# SimPL_IMU_v1_0_NOV23.net
KiCad netlist of a schematic drawn in Altium Designer
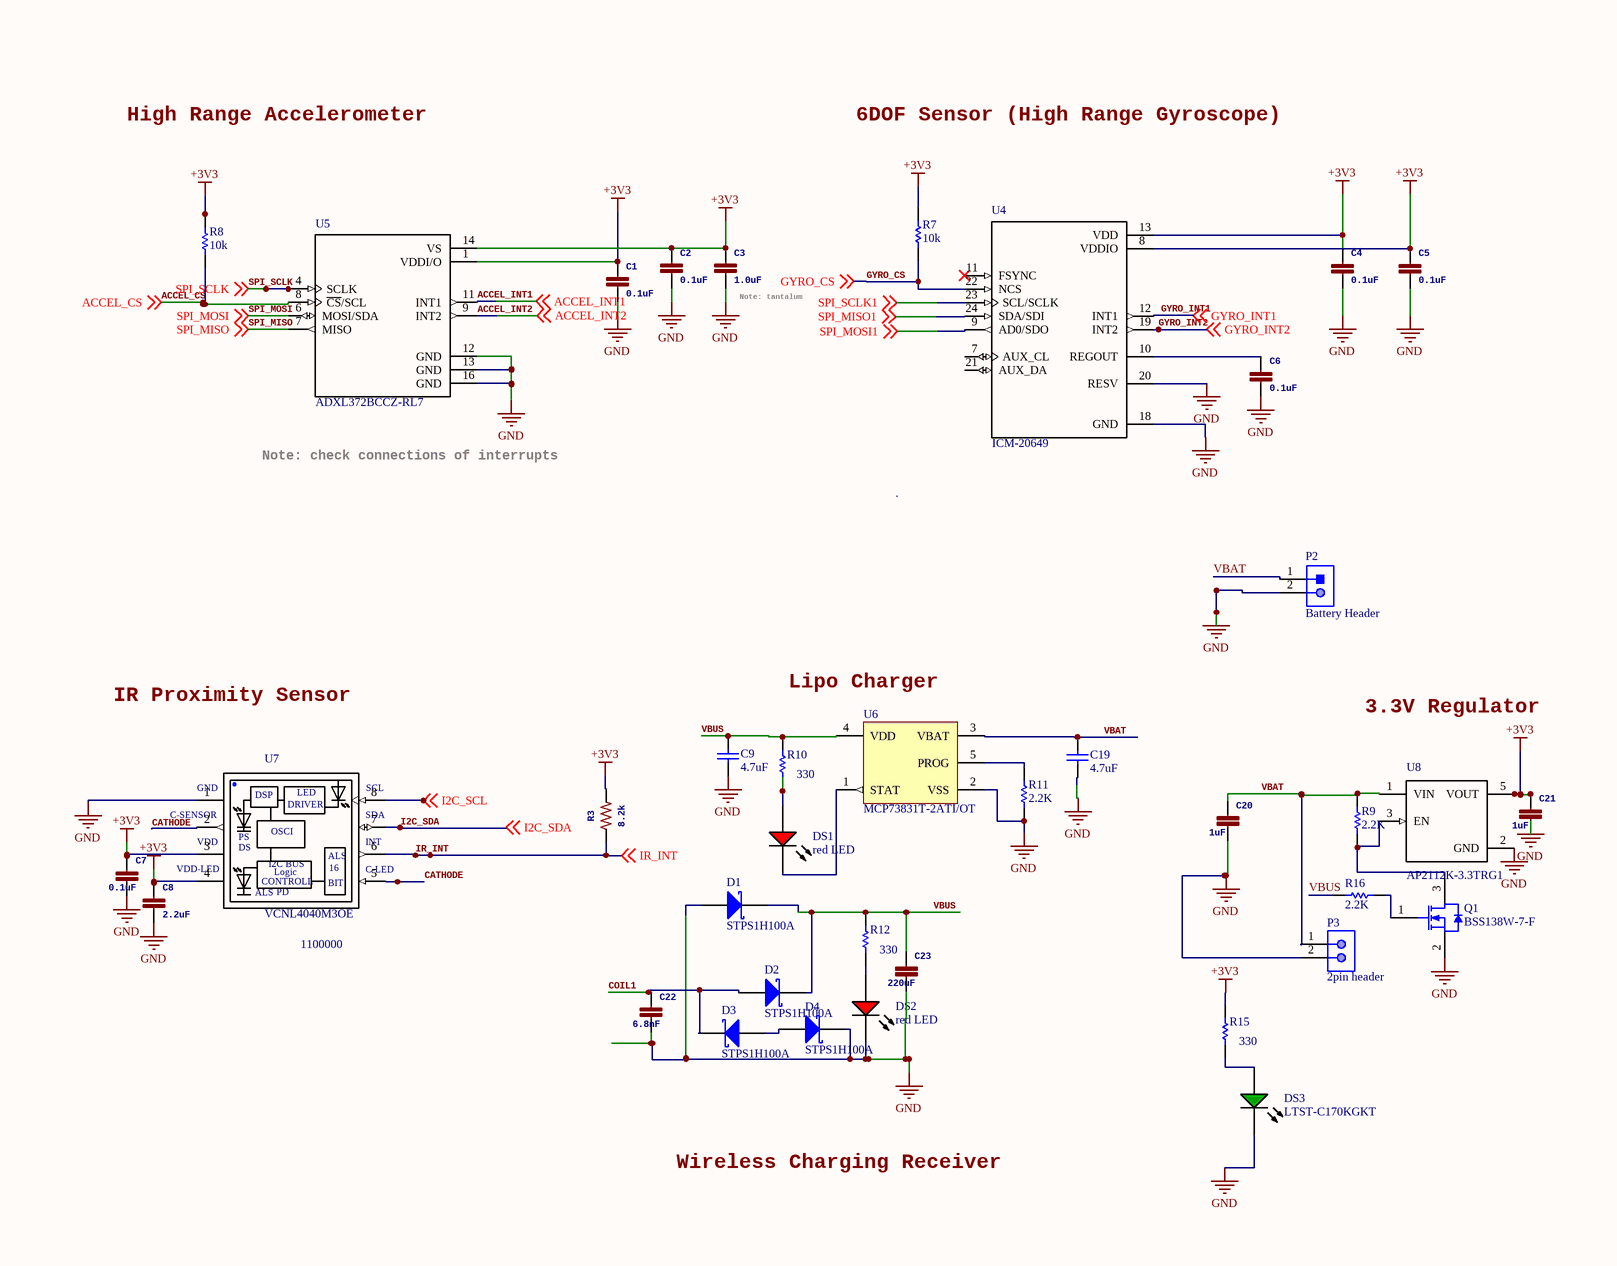
[diagram p0: SimPL_IMU_v1_0_NOV23.SchDoc]

(export (version "E")
  (design (tool "Eeschema 10.0.6"))
  (components
    (comp (ref "C1")
      (value "0.1uF")
      (footprint "0402")
      (libsource (lib "SparkFun-Capacitors") (part "0.1UF-0402-16V-10%"))
    )
    (comp (ref "C2")
      (value "0.1uF")
      (footprint "0402")
      (libsource (lib "SparkFun-Capacitors") (part "0.1UF-0402-16V-10%"))
    )
    (comp (ref "C3")
      (value "1.0uF")
      (footprint "0402")
      (libsource (lib "SparkFun-Capacitors") (part "1.0UF-0402-16V-10%"))
    )
    (comp (ref "C4")
      (value "0.1uF")
      (footprint "0402")
      (libsource (lib "SparkFun-Capacitors") (part "0.1UF-0402-16V-10%"))
    )
    (comp (ref "C5")
      (value "0.1uF")
      (footprint "0402")
      (libsource (lib "SparkFun-Capacitors") (part "0.1UF-0402-16V-10%"))
    )
    (comp (ref "C6")
      (value "0.1uF")
      (footprint "0402")
      (libsource (lib "SparkFun-Capacitors") (part "0.1UF-0402-16V-10%"))
    )
    (comp (ref "C7")
      (value "0.1uF")
      (footprint "0402")
      (libsource (lib "SparkFun-Capacitors") (part "0.1UF-0402-16V-10%"))
    )
    (comp (ref "C8")
      (value "2.2uF")
      (footprint "0402")
      (libsource (lib "SparkFun-Capacitors") (part "0.1UF-0402-16V-10%"))
    )
    (comp (ref "C9")
      (value "4.7uF")
      (footprint "CAPC1005X65X10ML15")
      (description "Chip Capacitor, 4.7 uF, +/- 20%, 10 V, -55 to 85 degC, 0402 (1005 Metric), RoHS, Tape and Reel")
      (fields
        (field (name "TOLERANCE") "±20%")
        (field (name "PCN PART NUMBER") "MLCCPartNumberChange30/Nov/2012")
      )
      (libsource (lib "Altium Content Vault") (part "CAP-NP-2"))
    )
    (comp (ref "C19")
      (value "4.7uF")
      (footprint "CAPC1005X65X10ML15")
      (description "Chip Capacitor, 4.7 uF, +/- 20%, 10 V, -55 to 85 degC, 0402 (1005 Metric), RoHS, Tape and Reel")
      (fields
        (field (name "TOLERANCE") "±20%")
        (field (name "PCN PART NUMBER") "MLCCPartNumberChange30/Nov/2012")
      )
      (libsource (lib "Altium Content Vault") (part "CAP-NP-2"))
    )
    (comp (ref "C20")
      (value "1uF")
      (footprint "0402")
      (libsource (lib "SparkFun-Capacitors") (part "0.1UF-0402-16V-10%"))
    )
    (comp (ref "C21")
      (value "1uF")
      (footprint "0402")
      (libsource (lib "SparkFun-Capacitors") (part "0.1UF-0402-16V-10%"))
    )
    (comp (ref "C22")
      (value "6.8nF")
      (footprint "0402")
      (libsource (lib "SparkFun-Capacitors") (part "0.1UF-0402-16V-10%"))
    )
    (comp (ref "C23")
      (value "220uF")
      (footprint "0402")
      (libsource (lib "SparkFun-Capacitors") (part "0.1UF-0402-16V-10%"))
    )
    (comp (ref "D1")
      (value "STPS1H100A")
      (footprint "STM-SMA-2_V")
      (description "High Voltage Power Schottky Rectifier, 1 A, 100 V, 2-Pin SMD (SMA), RoHS, Tape and Reel")
      (fields (field (name "MANUFACTURER") "STMicroelectronics"))
      (libsource (lib "Altium Content Vault") (part "DSKY-AK-2"))
    )
    (comp (ref "D2")
      (value "STPS1H100A")
      (footprint "STM-SMA-2_V")
      (description "High Voltage Power Schottky Rectifier, 1 A, 100 V, 2-Pin SMD (SMA), RoHS, Tape and Reel")
      (fields (field (name "MANUFACTURER") "STMicroelectronics"))
      (libsource (lib "Altium Content Vault") (part "DSKY-AK-2"))
    )
    (comp (ref "D3")
      (value "STPS1H100A")
      (footprint "STM-SMA-2_V")
      (description "High Voltage Power Schottky Rectifier, 1 A, 100 V, 2-Pin SMD (SMA), RoHS, Tape and Reel")
      (fields (field (name "MANUFACTURER") "STMicroelectronics"))
      (libsource (lib "Altium Content Vault") (part "DSKY-AK-2"))
    )
    (comp (ref "D4")
      (value "STPS1H100A")
      (footprint "STM-SMA-2_V")
      (description "High Voltage Power Schottky Rectifier, 1 A, 100 V, 2-Pin SMD (SMA), RoHS, Tape and Reel")
      (fields (field (name "MANUFACTURER") "STMicroelectronics"))
      (libsource (lib "Altium Content Vault") (part "DSKY-AK-2"))
    )
    (comp (ref "DS1")
      (value "red LED")
      (footprint "VISH-TLMS1000_V")
      (description "Low Current LED, 40 mW, 1.8 V, -40 to 100 degC, 2-Pin SMD (0603), RoHS, Tape and Reel")
      (fields (field (name "MANUFACTURER") "Vishay"))
      (libsource (lib "Altium Content Vault") (part "LED-RED-AK-2"))
    )
    (comp (ref "DS2")
      (value "red LED")
      (footprint "VISH-TLMS1000_V")
      (description "Low Current LED, 40 mW, 1.8 V, -40 to 100 degC, 2-Pin SMD (0603), RoHS, Tape and Reel")
      (fields (field (name "MANUFACTURER") "Vishay"))
      (libsource (lib "Altium Content Vault") (part "LED-RED-AK-2"))
    )
    (comp (ref "DS3")
      (value "LTST-C170KGKT")
      (footprint "LTST-LTST-C170KGKT-2_V")
      (description "Ultra Bright AlInGaP Chip LED, 75 mW, -55 to 85 degC, 2-Pin SMD (0805), RoHS, Tape and Reel")
      (fields (field (name "MANUFACTURER") "Lite-On"))
      (libsource (lib "Altium Content Vault") (part "LED-GREEN-KA-2"))
    )
    (comp (ref "P2")
      (value "Battery Header")
      (footprint "JST-S2B-PH-K-S_V")
      (fields (field (name "TOLERANCE") "20%"))
      (libsource (lib "Altium Content Vault") (part "CN-1P-M-R2"))
    )
    (comp (ref "P3")
      (value "2pin header")
      (footprint "AMPH-68000-102HLF_V")
      (description "Male Header, Pitch 2.54 mm, 1 x 2 Position, Height 8.38 mm, Tail Length 2.41 mm, RoHS, Bulk")
      (fields (field (name "MANUFACTURER") "FCI"))
      (libsource (lib "") (part "CN-1P-M-R2_1"))
    )
    (comp (ref "Q1")
      (value "BSS138W-7-F")
      (footprint "DIOD-SOT323-3_V")
      (fields (field (name "MANUFACTURER") "DiodesIncorporated"))
      (libsource (lib "Altium Content Vault") (part "NEMOS-GSD-3"))
    )
    (comp (ref "R3")
      (value "8.2k")
      (footprint "0603")
      (libsource (lib "SparkFun-Resistors") (part "8.2KOHM-0603-1/10W-5%"))
    )
    (comp (ref "R7")
      (value "10k")
      (footprint "RESC1005X40X25NL05T05")
      (description "Chip Resistor, 10 KOhm, +/- 1%, 100 mW, -55 to 155 degC, 0402 (1005 Metric), RoHS, Tape and Reel")
      (fields (field (name "MANUFACTURER") "Basic Passives") (field (name "TOLERANCE") "1%"))
      (libsource (lib "Altium Content Vault") (part "RES-2"))
    )
    (comp (ref "R8")
      (value "10k")
      (footprint "RESC1005X40X25NL05T05")
      (description "Chip Resistor, 10 KOhm, +/- 1%, 100 mW, -55 to 155 degC, 0402 (1005 Metric), RoHS, Tape and Reel")
      (fields (field (name "MANUFACTURER") "Basic Passives") (field (name "TOLERANCE") "1%"))
      (libsource (lib "Altium Content Vault") (part "RES-2"))
    )
    (comp (ref "R9")
      (value "2.2K")
      (footprint "RESC1005X40X25ML10T10")
      (fields (field (name "PART NUMBER") "MC00625W040212K2") (field (name "MANUFACTURER") "Multicomp"))
      (libsource (lib "Altium Content Vault") (part "RES"))
    )
    (comp (ref "R10")
      (value "330")
      (footprint "RESC2013X50X30NL20T20")
      (fields (field (name "MANUFACTURER") "Vishay Dale") (field (name "PART NUMBER") "CRCW0805330RFKEA"))
      (libsource (lib "Altium Content Vault") (part "RES"))
    )
    (comp (ref "R11")
      (value "2.2K")
      (footprint "RESC1005X40X25ML10T10")
      (fields (field (name "PART NUMBER") "MC00625W040212K2") (field (name "MANUFACTURER") "Multicomp"))
      (libsource (lib "Altium Content Vault") (part "RES"))
    )
    (comp (ref "R12")
      (value "330")
      (footprint "RESC2013X50X30NL20T20")
      (fields (field (name "MANUFACTURER") "Vishay Dale") (field (name "PART NUMBER") "CRCW0805330RFKEA"))
      (libsource (lib "Altium Content Vault") (part "RES"))
    )
    (comp (ref "R15")
      (value "330")
      (footprint "RESC2013X50X30NL20T20")
      (fields (field (name "MANUFACTURER") "Vishay Dale") (field (name "PART NUMBER") "CRCW0805330RFKEA"))
      (libsource (lib "Altium Content Vault") (part "RES"))
    )
    (comp (ref "R16")
      (value "2.2K")
      (footprint "RESC1005X40X25ML10T10")
      (fields (field (name "PART NUMBER") "MC00625W040212K2") (field (name "MANUFACTURER") "Multicomp"))
      (libsource (lib "Altium Content Vault") (part "RES"))
    )
    (comp (ref "U4")
      (value "ICM-20649")
      (footprint "*QFN40P300X300X95-24N")
      (description "Wide-Range 6-Axis MEMS MotionTracking Device for Sports and High Impact Applications")
      (fields (field (name "MF") "TDK InvenSense"))
      (libsource (lib "ICM-20649") (part "ICM-20649"))
    )
    (comp (ref "U5")
      (value "ADXL372BCCZ-RL7")
      (footprint "*PQFN50P322X300X114-16N")
      (description "Accelerometer Triple Â±200g 2.5V 16-Pin LGA T/R")
      (fields (field (name "MF") "Analog Devices"))
      (libsource (lib "ADXL372BCCZ-RL7") (part "ADXL372BCCZ-RL7"))
    )
    (comp (ref "U6")
      (value "MCP73831T-2ATI/OT")
      (footprint "SOT-23-OT5_M")
      (libsource (lib "Altium Content Vault") (part "PM-BM-MCP73831-SOT5"))
    )
    (comp (ref "U7")
      (value "VCNL4040M3OE")
      (footprint "*VISHAY_VCNL4040_4X2X1.1")
      (description "VCNL4040 Series 3.6 V 200 mm 16 Bit I2C SMT Proximity and Ambient Light Sensor")
      (fields (field (name "MF") "Vishay"))
      (libsource (lib "VCNL4040M3OE") (part "VCNL4040M3OE"))
    )
    (comp (ref "U8")
      (value "AP2112K-3.3TRG1")
      (footprint "*SOT95P285X140-5N")
      (description "AP2112 Series 0.6 A 3.3 V Fixed Output SMT LDO Linear Regulator - SOT23-5")
      (fields (field (name "MF") "Diodes Inc."))
      (libsource (lib "AP2112K-3.3TRG1") (part "AP2112K-3.3TRG1"))
    )
  )
  (nets
    (net (code "1") (name "+3V3") (class "Default")
      (node (ref "C1") (pin "1") (pinfunction "1_1") (pintype "passive"))
      (node (ref "C2") (pin "1") (pinfunction "1_1") (pintype "passive"))
      (node (ref "C21") (pin "1") (pinfunction "1_1") (pintype "passive"))
      (node (ref "C3") (pin "1") (pinfunction "1_1") (pintype "passive"))
      (node (ref "C4") (pin "1") (pinfunction "1_1") (pintype "passive"))
      (node (ref "C5") (pin "1") (pinfunction "1_1") (pintype "passive"))
      (node (ref "C7") (pin "1") (pinfunction "1_1") (pintype "passive"))
      (node (ref "C8") (pin "1") (pinfunction "1_1") (pintype "passive"))
      (node (ref "R15") (pin "2") (pinfunction "2_2") (pintype "passive"))
      (node (ref "R3") (pin "2") (pinfunction "2_2") (pintype "passive"))
      (node (ref "R7") (pin "2") (pinfunction "2_2") (pintype "passive"))
      (node (ref "R8") (pin "2") (pinfunction "2_2") (pintype "passive"))
      (node (ref "U4") (pin "13") (pinfunction "VDD_13") (pintype "power_in"))
      (node (ref "U4") (pin "8") (pinfunction "VDDIO_8") (pintype "power_in"))
      (node (ref "U5") (pin "1") (pinfunction "VDDI/O_1") (pintype "power_in"))
      (node (ref "U5") (pin "14") (pinfunction "VS_14") (pintype "power_in"))
      (node (ref "U7") (pin "3") (pinfunction "VDD_3") (pintype "power_in"))
      (node (ref "U7") (pin "4") (pinfunction "VDD-LED_4") (pintype "power_in"))
      (node (ref "U8") (pin "5") (pinfunction "VOUT_5") (pintype "power_in"))
    )
    (net (code "2") (name "/CATHODE") (class "Default")
      (node (ref "U7") (pin "2") (pinfunction "C-SENSOR_2") (pintype "output"))
      (node (ref "U7") (pin "5") (pinfunction "C-LED_5") (pintype "input"))
    )
    (net (code "3") (name "/COIL1") (class "Default")
      (node (ref "C22") (pin "1") (pinfunction "1_1") (pintype "passive"))
      (node (ref "D2") (pin "1") (pinfunction "A_1") (pintype "passive"))
      (node (ref "D3") (pin "2") (pinfunction "K_2") (pintype "passive"))
    )
    (net (code "4") (name "/VBAT") (class "Default")
      (node (ref "C19") (pin "2") (pinfunction "2_2") (pintype "passive"))
      (node (ref "C20") (pin "1") (pinfunction "1_1") (pintype "passive"))
      (node (ref "P2") (pin "1") (pinfunction "1_1") (pintype "passive"))
      (node (ref "P3") (pin "1") (pinfunction "1_1") (pintype "passive"))
      (node (ref "R9") (pin "2") (pinfunction "2_2") (pintype "passive"))
      (node (ref "U6") (pin "3") (pinfunction "VBAT_3") (pintype "power_in"))
      (node (ref "U8") (pin "1") (pinfunction "VIN_1") (pintype "power_in"))
    )
    (net (code "5") (name "/VBUS") (class "Default")
      (node (ref "C23") (pin "1") (pinfunction "1_1") (pintype "passive"))
      (node (ref "C9") (pin "2") (pinfunction "2_2") (pintype "passive"))
      (node (ref "D1") (pin "2") (pinfunction "K_2") (pintype "passive"))
      (node (ref "D2") (pin "2") (pinfunction "K_2") (pintype "passive"))
      (node (ref "R10") (pin "2") (pinfunction "2_2") (pintype "passive"))
      (node (ref "R12") (pin "2") (pinfunction "2_2") (pintype "passive"))
      (node (ref "R16") (pin "2") (pinfunction "2_2") (pintype "passive"))
      (node (ref "U6") (pin "4") (pinfunction "VDD_4") (pintype "power_in"))
    )
    (net (code "6") (name "ACCEL_CS") (class "Default")
      (node (ref "R8") (pin "1") (pinfunction "1_1") (pintype "passive"))
      (node (ref "U5") (pin "8") (pinfunction "~{CS}/SCL_8") (pintype "input"))
    )
    (net (code "7") (name "ACCEL_INT1") (class "Default")
      (node (ref "U5") (pin "11") (pinfunction "INT1_11") (pintype "output"))
    )
    (net (code "8") (name "ACCEL_INT2") (class "Default")
      (node (ref "U5") (pin "9") (pinfunction "INT2_9") (pintype "output"))
    )
    (net (code "9") (name "GND") (class "Default")
      (node (ref "C1") (pin "2") (pinfunction "2_2") (pintype "passive"))
      (node (ref "C19") (pin "1") (pinfunction "1_1") (pintype "passive"))
      (node (ref "C2") (pin "2") (pinfunction "2_2") (pintype "passive"))
      (node (ref "C20") (pin "2") (pinfunction "2_2") (pintype "passive"))
      (node (ref "C21") (pin "2") (pinfunction "2_2") (pintype "passive"))
      (node (ref "C22") (pin "2") (pinfunction "2_2") (pintype "passive"))
      (node (ref "C23") (pin "2") (pinfunction "2_2") (pintype "passive"))
      (node (ref "C3") (pin "2") (pinfunction "2_2") (pintype "passive"))
      (node (ref "C4") (pin "2") (pinfunction "2_2") (pintype "passive"))
      (node (ref "C5") (pin "2") (pinfunction "2_2") (pintype "passive"))
      (node (ref "C6") (pin "2") (pinfunction "2_2") (pintype "passive"))
      (node (ref "C7") (pin "2") (pinfunction "2_2") (pintype "passive"))
      (node (ref "C8") (pin "2") (pinfunction "2_2") (pintype "passive"))
      (node (ref "C9") (pin "1") (pinfunction "1_1") (pintype "passive"))
      (node (ref "D1") (pin "1") (pinfunction "A_1") (pintype "passive"))
      (node (ref "D4") (pin "2") (pinfunction "K_2") (pintype "passive"))
      (node (ref "DS2") (pin "2") (pinfunction "K_2") (pintype "passive"))
      (node (ref "DS3") (pin "1") (pinfunction "K_1") (pintype "passive"))
      (node (ref "P2") (pin "2") (pinfunction "2_2") (pintype "passive"))
      (node (ref "P3") (pin "2") (pinfunction "2_2") (pintype "passive"))
      (node (ref "Q1") (pin "2") (pinfunction "S_2") (pintype "passive"))
      (node (ref "R11") (pin "1") (pinfunction "1_1") (pintype "passive"))
      (node (ref "U4") (pin "18") (pinfunction "GND_18") (pintype "power_in"))
      (node (ref "U4") (pin "20") (pinfunction "RESV_20") (pintype "passive"))
      (node (ref "U5") (pin "12") (pinfunction "GND_12") (pintype "power_in"))
      (node (ref "U5") (pin "13") (pinfunction "GND_13") (pintype "power_in"))
      (node (ref "U5") (pin "16") (pinfunction "GND_16") (pintype "power_in"))
      (node (ref "U6") (pin "2") (pinfunction "VSS_2") (pintype "power_in"))
      (node (ref "U7") (pin "1") (pinfunction "GND_1") (pintype "power_in"))
      (node (ref "U8") (pin "2") (pinfunction "GND_2") (pintype "power_in"))
    )
    (net (code "10") (name "GYRO_CS") (class "Default")
      (node (ref "R7") (pin "1") (pinfunction "1_1") (pintype "passive"))
      (node (ref "U4") (pin "22") (pinfunction "NCS_22") (pintype "input"))
    )
    (net (code "11") (name "GYRO_INT1") (class "Default")
      (node (ref "U4") (pin "12") (pinfunction "INT1_12") (pintype "output"))
    )
    (net (code "12") (name "GYRO_INT2") (class "Default")
      (node (ref "U4") (pin "19") (pinfunction "INT2_19") (pintype "output"))
    )
    (net (code "13") (name "I2C_SCL") (class "Default")
      (node (ref "U7") (pin "8") (pinfunction "SCL_8") (pintype "input"))
    )
    (net (code "14") (name "I2C_SDA") (class "Default")
      (node (ref "U7") (pin "7") (pinfunction "SDA_7") (pintype "bidirectional"))
    )
    (net (code "15") (name "IR_INT") (class "Default")
      (node (ref "R3") (pin "1") (pinfunction "1_1") (pintype "passive"))
      (node (ref "U7") (pin "6") (pinfunction "INT_6") (pintype "output"))
    )
    (net (code "16") (name "Net-(D3-A)") (class "Default")
      (node (ref "D3") (pin "1") (pinfunction "A_1") (pintype "passive"))
      (node (ref "D4") (pin "1") (pinfunction "A_1") (pintype "passive"))
    )
    (net (code "17") (name "Net-(DS1-A)") (class "Default")
      (node (ref "DS1") (pin "1") (pinfunction "A_1") (pintype "passive"))
      (node (ref "R10") (pin "1") (pinfunction "1_1") (pintype "passive"))
    )
    (net (code "18") (name "Net-(DS1-K)") (class "Default")
      (node (ref "DS1") (pin "2") (pinfunction "K_2") (pintype "passive"))
      (node (ref "U6") (pin "1") (pinfunction "STAT_1") (pintype "output"))
    )
    (net (code "19") (name "Net-(DS2-A)") (class "Default")
      (node (ref "DS2") (pin "1") (pinfunction "A_1") (pintype "passive"))
      (node (ref "R12") (pin "1") (pinfunction "1_1") (pintype "passive"))
    )
    (net (code "20") (name "Net-(DS3-A)") (class "Default")
      (node (ref "DS3") (pin "2") (pinfunction "A_2") (pintype "passive"))
      (node (ref "R15") (pin "1") (pinfunction "1_1") (pintype "passive"))
    )
    (net (code "21") (name "Net-(Q1-D)") (class "Default")
      (node (ref "Q1") (pin "3") (pinfunction "D_3") (pintype "passive"))
      (node (ref "R9") (pin "1") (pinfunction "1_1") (pintype "passive"))
      (node (ref "U8") (pin "3") (pinfunction "EN_3") (pintype "input"))
    )
    (net (code "22") (name "Net-(Q1-G)") (class "Default")
      (node (ref "Q1") (pin "1") (pinfunction "G_1") (pintype "passive"))
      (node (ref "R16") (pin "1") (pinfunction "1_1") (pintype "passive"))
    )
    (net (code "23") (name "Net-(U4-REGOUT)") (class "Default")
      (node (ref "C6") (pin "1") (pinfunction "1_1") (pintype "passive"))
      (node (ref "U4") (pin "10") (pinfunction "REGOUT_10") (pintype "passive"))
    )
    (net (code "24") (name "Net-(U6-PROG)") (class "Default")
      (node (ref "R11") (pin "2") (pinfunction "2_2") (pintype "passive"))
      (node (ref "U6") (pin "5") (pinfunction "PROG_5") (pintype "passive"))
    )
    (net (code "25") (name "SPI_MISO") (class "Default")
      (node (ref "U5") (pin "7") (pinfunction "MISO_7") (pintype "output"))
    )
    (net (code "26") (name "SPI_MISO1") (class "Default")
      (node (ref "U4") (pin "24") (pinfunction "SDA/SDI_24") (pintype "input"))
    )
    (net (code "27") (name "SPI_MOSI") (class "Default")
      (node (ref "U5") (pin "6") (pinfunction "MOSI/SDA_6") (pintype "bidirectional"))
    )
    (net (code "28") (name "SPI_MOSI1") (class "Default")
      (node (ref "U4") (pin "9") (pinfunction "AD0/SDO_9") (pintype "output"))
    )
    (net (code "29") (name "SPI_SCLK") (class "Default")
      (node (ref "U5") (pin "4") (pinfunction "SCLK_4") (pintype "input"))
    )
    (net (code "30") (name "SPI_SCLK1") (class "Default")
      (node (ref "U4") (pin "23") (pinfunction "SCL/SCLK_23") (pintype "input"))
    )
    (net (code "31") (name "unconnected-(U4-AUX_CL-Pad7)") (class "Default")
      (node (ref "U4") (pin "7") (pinfunction "AUX_CL_7") (pintype "bidirectional"))
    )
    (net (code "32") (name "unconnected-(U4-AUX_DA-Pad21)") (class "Default")
      (node (ref "U4") (pin "21") (pinfunction "AUX_DA_21") (pintype "bidirectional"))
    )
    (net (code "33") (name "unconnected-(U4-FSYNC-Pad11)") (class "Default")
      (node (ref "U4") (pin "11") (pinfunction "FSYNC_11") (pintype "input+no_connect"))
    )
  )
)
